# adsr_v3.net
KiCad netlist of a schematic drawn in EAGLE
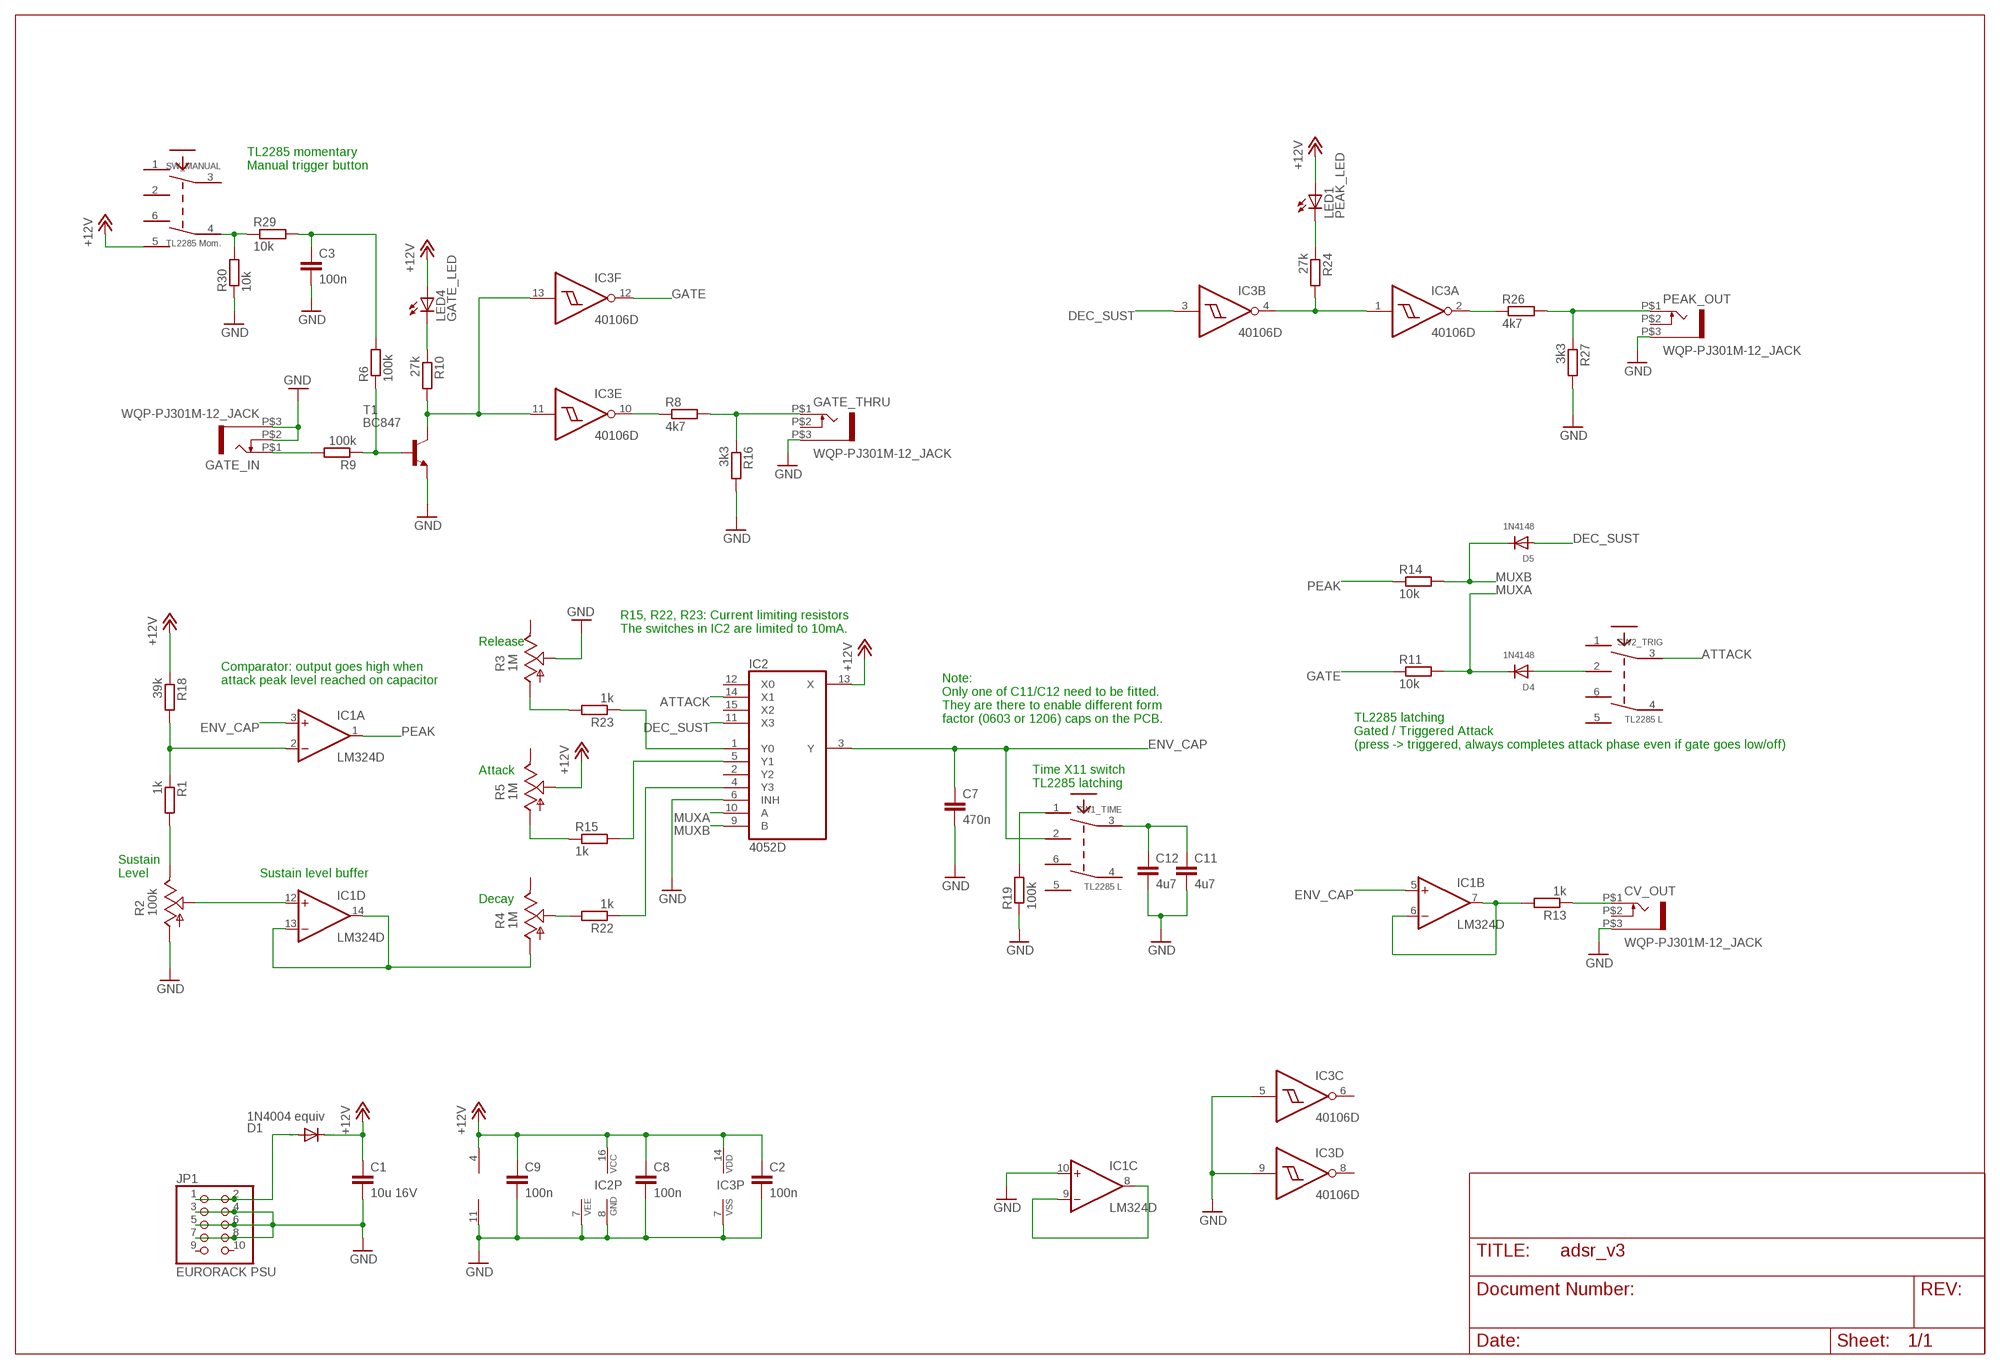
[diagram p0: schematic, sheet 1]

(export (version "E")
  (design (tool "Eeschema 10.0.6"))
  (components
    (comp (ref "C1")
      (value "10u 16V")
      (footprint "eagle-import:C1206K")
      (libsource (lib "eagle-import") (part "C-EUC1206K"))
    )
    (comp (ref "C2")
      (value "100n")
      (footprint "eagle-import:C0603K")
      (libsource (lib "eagle-import") (part "C-EUC0603K"))
    )
    (comp (ref "C3")
      (value "100n")
      (footprint "eagle-import:C0603K")
      (libsource (lib "eagle-import") (part "C-EUC0603K"))
    )
    (comp (ref "C7")
      (value "470n")
      (footprint "eagle-import:C0603K")
      (libsource (lib "eagle-import") (part "C-EUC0603K"))
    )
    (comp (ref "C8")
      (value "100n")
      (footprint "eagle-import:C0603K")
      (libsource (lib "eagle-import") (part "C-EUC0603K"))
    )
    (comp (ref "C9")
      (value "100n")
      (footprint "eagle-import:C0603K")
      (libsource (lib "eagle-import") (part "C-EUC0603K"))
    )
    (comp (ref "C11")
      (value "4u7")
      (footprint "eagle-import:C1206K")
      (libsource (lib "eagle-import") (part "C-EUC1206K"))
    )
    (comp (ref "C12")
      (value "4u7")
      (footprint "eagle-import:C0603K")
      (libsource (lib "eagle-import") (part "C-EUC0603K"))
    )
    (comp (ref "CV_OUT")
      (value "WQP-PJ301M-12_JACK")
      (footprint "eagle-import:WQP-PJ301M-12_JACK")
      (libsource (lib "eagle-import") (part "WQP-PJ301M-12_JACK"))
    )
    (comp (ref "D1")
      (value "1N4004 equiv")
      (footprint "eagle-import:DO214AA")
      (libsource (lib "eagle-import") (part "DIODE-DO214AA"))
    )
    (comp (ref "D4")
      (value "1N4148")
      (footprint "eagle-import:SOD-323F")
      (libsource (lib "eagle-import") (part "DIODESOD-323F"))
    )
    (comp (ref "D5")
      (value "1N4148")
      (footprint "eagle-import:SOD-323F")
      (libsource (lib "eagle-import") (part "DIODESOD-323F"))
    )
    (comp (ref "GATE_IN")
      (value "WQP-PJ301M-12_JACK")
      (footprint "eagle-import:WQP-PJ301M-12_JACK")
      (libsource (lib "eagle-import") (part "WQP-PJ301M-12_JACK"))
    )
    (comp (ref "GATE_THRU")
      (value "WQP-PJ301M-12_JACK")
      (footprint "eagle-import:WQP-PJ301M-12_JACK")
      (libsource (lib "eagle-import") (part "WQP-PJ301M-12_JACK"))
    )
    (comp (ref "IC1")
      (value "LM324D")
      (footprint "eagle-import:SO14")
      (libsource (lib "eagle-import") (part "LM324D"))
    )
    (comp (ref "IC2")
      (value "4052D")
      (footprint "eagle-import:SO16")
      (libsource (lib "eagle-import") (part "4052D"))
    )
    (comp (ref "IC3")
      (value "40106D")
      (footprint "eagle-import:SO14")
      (libsource (lib "eagle-import") (part "40106D"))
    )
    (comp (ref "JP1")
      (value "EURORACK PSU")
      (footprint "eagle-import:2X05")
      (libsource (lib "eagle-import") (part "PINHD-2X5"))
    )
    (comp (ref "LED1")
      (value "PEAK_LED")
      (footprint "eagle-import:LED5MM")
      (libsource (lib "eagle-import") (part "LED5MM"))
    )
    (comp (ref "LED4")
      (value "GATE_LED")
      (footprint "eagle-import:LED5MM")
      (libsource (lib "eagle-import") (part "LED5MM"))
    )
    (comp (ref "PEAK_OUT")
      (value "WQP-PJ301M-12_JACK")
      (footprint "eagle-import:WQP-PJ301M-12_JACK")
      (libsource (lib "eagle-import") (part "WQP-PJ301M-12_JACK"))
    )
    (comp (ref "R1")
      (value "1k")
      (footprint "eagle-import:R0603")
      (libsource (lib "eagle-import") (part "R-EU_R0603"))
    )
    (comp (ref "R2")
      (value "100k")
      (footprint "eagle-import:ALPS_POT_VERTICAL")
      (libsource (lib "eagle-import") (part "POT_USVERTICAL"))
    )
    (comp (ref "R3")
      (value "1M")
      (footprint "eagle-import:ALPS_POT_VERTICAL")
      (libsource (lib "eagle-import") (part "POT_USVERTICAL"))
    )
    (comp (ref "R4")
      (value "1M")
      (footprint "eagle-import:ALPS_POT_VERTICAL")
      (libsource (lib "eagle-import") (part "POT_USVERTICAL"))
    )
    (comp (ref "R5")
      (value "1M")
      (footprint "eagle-import:ALPS_POT_VERTICAL")
      (libsource (lib "eagle-import") (part "POT_USVERTICAL"))
    )
    (comp (ref "R6")
      (value "100k")
      (footprint "eagle-import:R0603")
      (libsource (lib "eagle-import") (part "R-EU_R0603"))
    )
    (comp (ref "R8")
      (value "4k7")
      (footprint "eagle-import:R0603")
      (libsource (lib "eagle-import") (part "R-EU_R0603"))
    )
    (comp (ref "R9")
      (value "100k")
      (footprint "eagle-import:R0603")
      (libsource (lib "eagle-import") (part "R-EU_R0603"))
    )
    (comp (ref "R10")
      (value "27k")
      (footprint "eagle-import:R0603")
      (libsource (lib "eagle-import") (part "R-EU_R0603"))
    )
    (comp (ref "R11")
      (value "10k")
      (footprint "eagle-import:R0603")
      (libsource (lib "eagle-import") (part "R-EU_R0603"))
    )
    (comp (ref "R13")
      (value "1k")
      (footprint "eagle-import:R0603")
      (libsource (lib "eagle-import") (part "R-EU_R0603"))
    )
    (comp (ref "R14")
      (value "10k")
      (footprint "eagle-import:R0603")
      (libsource (lib "eagle-import") (part "R-EU_R0603"))
    )
    (comp (ref "R15")
      (value "1k")
      (footprint "eagle-import:R0603")
      (libsource (lib "eagle-import") (part "R-EU_R0603"))
    )
    (comp (ref "R16")
      (value "3k3")
      (footprint "eagle-import:R0603")
      (libsource (lib "eagle-import") (part "R-EU_R0603"))
    )
    (comp (ref "R18")
      (value "39k")
      (footprint "eagle-import:R0603")
      (libsource (lib "eagle-import") (part "R-EU_R0603"))
    )
    (comp (ref "R19")
      (value "100k")
      (footprint "eagle-import:R0603")
      (libsource (lib "eagle-import") (part "R-EU_R0603"))
    )
    (comp (ref "R22")
      (value "1k")
      (footprint "eagle-import:R0603")
      (libsource (lib "eagle-import") (part "R-EU_R0603"))
    )
    (comp (ref "R23")
      (value "1k")
      (footprint "eagle-import:R0603")
      (libsource (lib "eagle-import") (part "R-EU_R0603"))
    )
    (comp (ref "R24")
      (value "27k")
      (footprint "eagle-import:R0603")
      (libsource (lib "eagle-import") (part "R-EU_R0603"))
    )
    (comp (ref "R26")
      (value "4k7")
      (footprint "eagle-import:R0603")
      (libsource (lib "eagle-import") (part "R-EU_R0603"))
    )
    (comp (ref "R27")
      (value "3k3")
      (footprint "eagle-import:R0603")
      (libsource (lib "eagle-import") (part "R-EU_R0603"))
    )
    (comp (ref "R29")
      (value "10k")
      (footprint "eagle-import:R0603")
      (libsource (lib "eagle-import") (part "R-EU_R0603"))
    )
    (comp (ref "R30")
      (value "10k")
      (footprint "eagle-import:R0603")
      (libsource (lib "eagle-import") (part "R-EU_R0603"))
    )
    (comp (ref "SW1_TIME")
      (value "TL2285 L")
      (footprint "eagle-import:TL2285_PCB")
      (libsource (lib "eagle-import") (part "TL2285"))
    )
    (comp (ref "SW2_TRIG")
      (value "TL2285 L")
      (footprint "eagle-import:TL2285_PCB")
      (libsource (lib "eagle-import") (part "TL2285"))
    )
    (comp (ref "SW_MANUAL")
      (value "TL2285 Mom.")
      (footprint "eagle-import:TL2285_PCB")
      (libsource (lib "eagle-import") (part "TL2285"))
    )
    (comp (ref "T1")
      (value "BC847")
      (footprint "eagle-import:SOT23")
      (libsource (lib "eagle-import") (part "BC847"))
    )
  )
  (nets
    (net (code "1") (name "+12V") (class "Default")
      (node (ref "C1") (pin "1") (pinfunction "1_1") (pintype "passive"))
      (node (ref "C2") (pin "1") (pinfunction "1_1") (pintype "passive"))
      (node (ref "C8") (pin "1") (pinfunction "1_1") (pintype "passive"))
      (node (ref "C9") (pin "1") (pinfunction "1_1") (pintype "passive"))
      (node (ref "D1") (pin "C") (pinfunction "C_C") (pintype "passive"))
      (node (ref "IC1") (pin "4") (pinfunction "V+_4") (pintype "power_in"))
      (node (ref "IC2") (pin "13") (pinfunction "X_13") (pintype "bidirectional"))
      (node (ref "IC2") (pin "16") (pinfunction "VCC_16") (pintype "power_in"))
      (node (ref "IC3") (pin "14") (pinfunction "VDD_14") (pintype "power_in"))
      (node (ref "LED1") (pin "A") (pinfunction "A_A") (pintype "passive"))
      (node (ref "LED4") (pin "A") (pinfunction "A_A") (pintype "passive"))
      (node (ref "R18") (pin "1") (pinfunction "1_1") (pintype "passive"))
      (node (ref "R5") (pin "P$2") (pinfunction "S_P$2") (pintype "passive"))
      (node (ref "SW_MANUAL") (pin "5") (pinfunction "P5_5") (pintype "bidirectional"))
    )
    (net (code "2") (name "/ATTACK") (class "Default")
      (node (ref "IC2") (pin "14") (pinfunction "X1_14") (pintype "bidirectional"))
      (node (ref "SW2_TRIG") (pin "3") (pinfunction "P3_3") (pintype "bidirectional"))
    )
    (net (code "3") (name "/DEC_SUST") (class "Default")
      (node (ref "D5") (pin "A") (pinfunction "A_A") (pintype "passive"))
      (node (ref "IC2") (pin "11") (pinfunction "X3_11") (pintype "bidirectional"))
      (node (ref "IC3") (pin "3") (pinfunction "I_3") (pintype "input"))
    )
    (net (code "4") (name "/ENV_CAP") (class "Default")
      (node (ref "C7") (pin "1") (pinfunction "1_1") (pintype "passive"))
      (node (ref "IC1") (pin "3") (pinfunction "+IN_3") (pintype "input"))
      (node (ref "IC1") (pin "5") (pinfunction "+IN_5") (pintype "input"))
      (node (ref "IC2") (pin "3") (pinfunction "Y_3") (pintype "bidirectional"))
      (node (ref "SW1_TIME") (pin "2") (pinfunction "P2_2") (pintype "bidirectional"))
    )
    (net (code "5") (name "/GATE") (class "Default")
      (node (ref "IC3") (pin "12") (pinfunction "O_12") (pintype "output"))
      (node (ref "R11") (pin "1") (pinfunction "1_1") (pintype "passive"))
    )
    (net (code "6") (name "/MUXA") (class "Default")
      (node (ref "D4") (pin "C") (pinfunction "C_C") (pintype "passive"))
      (node (ref "IC2") (pin "10") (pinfunction "A_10") (pintype "input"))
      (node (ref "R11") (pin "2") (pinfunction "2_2") (pintype "passive"))
    )
    (net (code "7") (name "/MUXB") (class "Default")
      (node (ref "D5") (pin "C") (pinfunction "C_C") (pintype "passive"))
      (node (ref "IC2") (pin "9") (pinfunction "B_9") (pintype "input"))
      (node (ref "R14") (pin "2") (pinfunction "2_2") (pintype "passive"))
    )
    (net (code "8") (name "/PEAK") (class "Default")
      (node (ref "IC1") (pin "1") (pinfunction "OUT_1") (pintype "output"))
      (node (ref "R14") (pin "1") (pinfunction "1_1") (pintype "passive"))
    )
    (net (code "9") (name "GND") (class "Default")
      (node (ref "C1") (pin "2") (pinfunction "2_2") (pintype "passive"))
      (node (ref "C11") (pin "2") (pinfunction "2_2") (pintype "passive"))
      (node (ref "C12") (pin "2") (pinfunction "2_2") (pintype "passive"))
      (node (ref "C2") (pin "2") (pinfunction "2_2") (pintype "passive"))
      (node (ref "C3") (pin "2") (pinfunction "2_2") (pintype "passive"))
      (node (ref "C7") (pin "2") (pinfunction "2_2") (pintype "passive"))
      (node (ref "C8") (pin "2") (pinfunction "2_2") (pintype "passive"))
      (node (ref "C9") (pin "2") (pinfunction "2_2") (pintype "passive"))
      (node (ref "CV_OUT") (pin "P$3") (pinfunction "1_P$3") (pintype "passive"))
      (node (ref "GATE_IN") (pin "P$2") (pinfunction "3_P$2") (pintype "passive"))
      (node (ref "GATE_IN") (pin "P$3") (pinfunction "1_P$3") (pintype "passive"))
      (node (ref "GATE_THRU") (pin "P$3") (pinfunction "1_P$3") (pintype "passive"))
      (node (ref "IC1") (pin "10") (pinfunction "+IN_10") (pintype "input"))
      (node (ref "IC1") (pin "11") (pinfunction "V-_11") (pintype "power_in"))
      (node (ref "IC2") (pin "6") (pinfunction "INH_6") (pintype "input"))
      (node (ref "IC2") (pin "7") (pinfunction "VEE_7") (pintype "power_in"))
      (node (ref "IC2") (pin "8") (pinfunction "GND_8") (pintype "power_in"))
      (node (ref "IC3") (pin "5") (pinfunction "I_5") (pintype "input"))
      (node (ref "IC3") (pin "7") (pinfunction "VSS_7") (pintype "power_in"))
      (node (ref "IC3") (pin "9") (pinfunction "I_9") (pintype "input"))
      (node (ref "JP1") (pin "3") (pinfunction "3_3") (pintype "passive"))
      (node (ref "JP1") (pin "4") (pinfunction "4_4") (pintype "passive"))
      (node (ref "JP1") (pin "5") (pinfunction "5_5") (pintype "passive"))
      (node (ref "JP1") (pin "6") (pinfunction "6_6") (pintype "passive"))
      (node (ref "JP1") (pin "7") (pinfunction "7_7") (pintype "passive"))
      (node (ref "JP1") (pin "8") (pinfunction "8_8") (pintype "passive"))
      (node (ref "PEAK_OUT") (pin "P$3") (pinfunction "1_P$3") (pintype "passive"))
      (node (ref "R16") (pin "2") (pinfunction "2_2") (pintype "passive"))
      (node (ref "R19") (pin "1") (pinfunction "1_1") (pintype "passive"))
      (node (ref "R2") (pin "P$3") (pinfunction "A_P$3") (pintype "passive"))
      (node (ref "R27") (pin "2") (pinfunction "2_2") (pintype "passive"))
      (node (ref "R3") (pin "P$2") (pinfunction "S_P$2") (pintype "passive"))
      (node (ref "R30") (pin "1") (pinfunction "1_1") (pintype "passive"))
      (node (ref "T1") (pin "2") (pinfunction "E_2") (pintype "passive"))
    )
    (net (code "10") (name "Net-(C3-Pad1)") (class "Default")
      (node (ref "C3") (pin "1") (pinfunction "1_1") (pintype "passive"))
      (node (ref "R29") (pin "2") (pinfunction "2_2") (pintype "passive"))
      (node (ref "R6") (pin "2") (pinfunction "2_2") (pintype "passive"))
    )
    (net (code "11") (name "Net-(CV_OUT-2)") (class "Default")
      (node (ref "CV_OUT") (pin "P$1") (pinfunction "2_P$1") (pintype "passive"))
      (node (ref "R13") (pin "1") (pinfunction "1_1") (pintype "passive"))
    )
    (net (code "12") (name "Net-(D1-PadA)") (class "Default")
      (node (ref "D1") (pin "A") (pinfunction "A_A") (pintype "passive"))
      (node (ref "JP1") (pin "1") (pinfunction "1_1") (pintype "passive"))
      (node (ref "JP1") (pin "2") (pinfunction "2_2") (pintype "passive"))
    )
    (net (code "13") (name "Net-(GATE_IN-2)") (class "Default")
      (node (ref "GATE_IN") (pin "P$1") (pinfunction "2_P$1") (pintype "passive"))
      (node (ref "R9") (pin "2") (pinfunction "2_2") (pintype "passive"))
    )
    (net (code "14") (name "Net-(GATE_THRU-2)") (class "Default")
      (node (ref "GATE_THRU") (pin "P$1") (pinfunction "2_P$1") (pintype "passive"))
      (node (ref "R16") (pin "1") (pinfunction "1_1") (pintype "passive"))
      (node (ref "R8") (pin "2") (pinfunction "2_2") (pintype "passive"))
    )
    (net (code "15") (name "Net-(IC1A--IN)") (class "Default")
      (node (ref "IC1") (pin "2") (pinfunction "-IN_2") (pintype "input"))
      (node (ref "R1") (pin "1") (pinfunction "1_1") (pintype "passive"))
      (node (ref "R18") (pin "2") (pinfunction "2_2") (pintype "passive"))
    )
    (net (code "16") (name "Net-(IC1B--IN)") (class "Default")
      (node (ref "IC1") (pin "6") (pinfunction "-IN_6") (pintype "input"))
      (node (ref "IC1") (pin "7") (pinfunction "OUT_7") (pintype "output"))
      (node (ref "R13") (pin "2") (pinfunction "2_2") (pintype "passive"))
    )
    (net (code "17") (name "Net-(IC1C--IN)") (class "Default")
      (node (ref "IC1") (pin "8") (pinfunction "OUT_8") (pintype "output"))
      (node (ref "IC1") (pin "9") (pinfunction "-IN_9") (pintype "input"))
    )
    (net (code "18") (name "Net-(IC1D-+IN)") (class "Default")
      (node (ref "IC1") (pin "12") (pinfunction "+IN_12") (pintype "input"))
      (node (ref "R2") (pin "P$2") (pinfunction "S_P$2") (pintype "passive"))
    )
    (net (code "19") (name "Net-(IC1D--IN)") (class "Default")
      (node (ref "IC1") (pin "13") (pinfunction "-IN_13") (pintype "input"))
      (node (ref "IC1") (pin "14") (pinfunction "OUT_14") (pintype "output"))
      (node (ref "R4") (pin "P$3") (pinfunction "A_P$3") (pintype "passive"))
    )
    (net (code "20") (name "Net-(IC2A-Y0)") (class "Default")
      (node (ref "IC2") (pin "1") (pinfunction "Y0_1") (pintype "bidirectional"))
      (node (ref "R23") (pin "1") (pinfunction "1_1") (pintype "passive"))
    )
    (net (code "21") (name "Net-(IC2A-Y1)") (class "Default")
      (node (ref "IC2") (pin "5") (pinfunction "Y1_5") (pintype "bidirectional"))
      (node (ref "R15") (pin "2") (pinfunction "2_2") (pintype "passive"))
    )
    (net (code "22") (name "Net-(IC2A-Y3)") (class "Default")
      (node (ref "IC2") (pin "4") (pinfunction "Y3_4") (pintype "bidirectional"))
      (node (ref "R22") (pin "1") (pinfunction "1_1") (pintype "passive"))
    )
    (net (code "23") (name "Net-(IC3A-I)") (class "Default")
      (node (ref "IC3") (pin "1") (pinfunction "I_1") (pintype "input"))
      (node (ref "IC3") (pin "4") (pinfunction "O_4") (pintype "output"))
      (node (ref "R24") (pin "2") (pinfunction "2_2") (pintype "passive"))
    )
    (net (code "24") (name "Net-(IC3A-O)") (class "Default")
      (node (ref "IC3") (pin "2") (pinfunction "O_2") (pintype "output"))
      (node (ref "R26") (pin "1") (pinfunction "1_1") (pintype "passive"))
    )
    (net (code "25") (name "Net-(IC3E-I)") (class "Default")
      (node (ref "IC3") (pin "11") (pinfunction "I_11") (pintype "input"))
      (node (ref "IC3") (pin "13") (pinfunction "I_13") (pintype "input"))
      (node (ref "R10") (pin "2") (pinfunction "2_2") (pintype "passive"))
      (node (ref "T1") (pin "3") (pinfunction "C_3") (pintype "passive"))
    )
    (net (code "26") (name "Net-(IC3E-O)") (class "Default")
      (node (ref "IC3") (pin "10") (pinfunction "O_10") (pintype "output"))
      (node (ref "R8") (pin "1") (pinfunction "1_1") (pintype "passive"))
    )
    (net (code "27") (name "Net-(LED1-C)") (class "Default")
      (node (ref "LED1") (pin "K") (pinfunction "C_K") (pintype "passive"))
      (node (ref "R24") (pin "1") (pinfunction "1_1") (pintype "passive"))
    )
    (net (code "28") (name "Net-(LED4-C)") (class "Default")
      (node (ref "LED4") (pin "K") (pinfunction "C_K") (pintype "passive"))
      (node (ref "R10") (pin "1") (pinfunction "1_1") (pintype "passive"))
    )
    (net (code "29") (name "Net-(PEAK_OUT-2)") (class "Default")
      (node (ref "PEAK_OUT") (pin "P$1") (pinfunction "2_P$1") (pintype "passive"))
      (node (ref "R26") (pin "2") (pinfunction "2_2") (pintype "passive"))
      (node (ref "R27") (pin "1") (pinfunction "1_1") (pintype "passive"))
    )
    (net (code "30") (name "Net-(R2-E)") (class "Default")
      (node (ref "R1") (pin "2") (pinfunction "2_2") (pintype "passive"))
      (node (ref "R2") (pin "P$1") (pinfunction "E_P$1") (pintype "passive"))
    )
    (net (code "31") (name "Net-(R3-A)") (class "Default")
      (node (ref "R23") (pin "2") (pinfunction "2_2") (pintype "passive"))
      (node (ref "R3") (pin "P$3") (pinfunction "A_P$3") (pintype "passive"))
    )
    (net (code "32") (name "Net-(R4-S)") (class "Default")
      (node (ref "R22") (pin "2") (pinfunction "2_2") (pintype "passive"))
      (node (ref "R4") (pin "P$2") (pinfunction "S_P$2") (pintype "passive"))
    )
    (net (code "33") (name "Net-(R5-A)") (class "Default")
      (node (ref "R15") (pin "1") (pinfunction "1_1") (pintype "passive"))
      (node (ref "R5") (pin "P$3") (pinfunction "A_P$3") (pintype "passive"))
    )
    (net (code "34") (name "Net-(SW1_TIME-P1)") (class "Default")
      (node (ref "R19") (pin "2") (pinfunction "2_2") (pintype "passive"))
      (node (ref "SW1_TIME") (pin "1") (pinfunction "P1_1") (pintype "bidirectional"))
    )
    (net (code "35") (name "Net-(SW1_TIME-P3)") (class "Default")
      (node (ref "C11") (pin "1") (pinfunction "1_1") (pintype "passive"))
      (node (ref "C12") (pin "1") (pinfunction "1_1") (pintype "passive"))
      (node (ref "SW1_TIME") (pin "3") (pinfunction "P3_3") (pintype "bidirectional"))
    )
    (net (code "36") (name "Net-(SW2_TRIG-P2)") (class "Default")
      (node (ref "D4") (pin "A") (pinfunction "A_A") (pintype "passive"))
      (node (ref "SW2_TRIG") (pin "2") (pinfunction "P2_2") (pintype "bidirectional"))
    )
    (net (code "37") (name "Net-(SW_MANUAL-P4)") (class "Default")
      (node (ref "R29") (pin "1") (pinfunction "1_1") (pintype "passive"))
      (node (ref "R30") (pin "2") (pinfunction "2_2") (pintype "passive"))
      (node (ref "SW_MANUAL") (pin "4") (pinfunction "P4_4") (pintype "bidirectional"))
    )
    (net (code "38") (name "Net-(T1-B)") (class "Default")
      (node (ref "R6") (pin "1") (pinfunction "1_1") (pintype "passive"))
      (node (ref "R9") (pin "1") (pinfunction "1_1") (pintype "passive"))
      (node (ref "T1") (pin "1") (pinfunction "B_1") (pintype "passive"))
    )
    (net (code "39") (name "unconnected-(CV_OUT-3-PadP$2)") (class "Default")
      (node (ref "CV_OUT") (pin "P$2") (pinfunction "3_P$2") (pintype "passive"))
    )
    (net (code "40") (name "unconnected-(GATE_THRU-3-PadP$2)") (class "Default")
      (node (ref "GATE_THRU") (pin "P$2") (pinfunction "3_P$2") (pintype "passive"))
    )
    (net (code "41") (name "unconnected-(IC2A-X0-Pad12)") (class "Default")
      (node (ref "IC2") (pin "12") (pinfunction "X0_12") (pintype "bidirectional"))
    )
    (net (code "42") (name "unconnected-(IC2A-X2-Pad15)") (class "Default")
      (node (ref "IC2") (pin "15") (pinfunction "X2_15") (pintype "bidirectional"))
    )
    (net (code "43") (name "unconnected-(IC2A-Y2-Pad2)") (class "Default")
      (node (ref "IC2") (pin "2") (pinfunction "Y2_2") (pintype "bidirectional"))
    )
    (net (code "44") (name "unconnected-(IC3C-O-Pad6)") (class "Default")
      (node (ref "IC3") (pin "6") (pinfunction "O_6") (pintype "output"))
    )
    (net (code "45") (name "unconnected-(IC3D-O-Pad8)") (class "Default")
      (node (ref "IC3") (pin "8") (pinfunction "O_8") (pintype "output"))
    )
    (net (code "46") (name "unconnected-(JP1-Pad9)") (class "Default")
      (node (ref "JP1") (pin "9") (pinfunction "9_9") (pintype "passive"))
    )
    (net (code "47") (name "unconnected-(JP1-Pad10)") (class "Default")
      (node (ref "JP1") (pin "10") (pinfunction "10_10") (pintype "passive"))
    )
    (net (code "48") (name "unconnected-(PEAK_OUT-3-PadP$2)") (class "Default")
      (node (ref "PEAK_OUT") (pin "P$2") (pinfunction "3_P$2") (pintype "passive"))
    )
    (net (code "49") (name "unconnected-(R3-E-PadP$1)") (class "Default")
      (node (ref "R3") (pin "P$1") (pinfunction "E_P$1") (pintype "passive"))
    )
    (net (code "50") (name "unconnected-(R4-E-PadP$1)") (class "Default")
      (node (ref "R4") (pin "P$1") (pinfunction "E_P$1") (pintype "passive"))
    )
    (net (code "51") (name "unconnected-(R5-E-PadP$1)") (class "Default")
      (node (ref "R5") (pin "P$1") (pinfunction "E_P$1") (pintype "passive"))
    )
    (net (code "52") (name "unconnected-(SW1_TIME-P4-Pad4)") (class "Default")
      (node (ref "SW1_TIME") (pin "4") (pinfunction "P4_4") (pintype "bidirectional"))
    )
    (net (code "53") (name "unconnected-(SW1_TIME-P5-Pad5)") (class "Default")
      (node (ref "SW1_TIME") (pin "5") (pinfunction "P5_5") (pintype "bidirectional"))
    )
    (net (code "54") (name "unconnected-(SW1_TIME-P6-Pad6)") (class "Default")
      (node (ref "SW1_TIME") (pin "6") (pinfunction "P6_6") (pintype "bidirectional"))
    )
    (net (code "55") (name "unconnected-(SW2_TRIG-P1-Pad1)") (class "Default")
      (node (ref "SW2_TRIG") (pin "1") (pinfunction "P1_1") (pintype "bidirectional"))
    )
    (net (code "56") (name "unconnected-(SW2_TRIG-P4-Pad4)") (class "Default")
      (node (ref "SW2_TRIG") (pin "4") (pinfunction "P4_4") (pintype "bidirectional"))
    )
    (net (code "57") (name "unconnected-(SW2_TRIG-P5-Pad5)") (class "Default")
      (node (ref "SW2_TRIG") (pin "5") (pinfunction "P5_5") (pintype "bidirectional"))
    )
    (net (code "58") (name "unconnected-(SW2_TRIG-P6-Pad6)") (class "Default")
      (node (ref "SW2_TRIG") (pin "6") (pinfunction "P6_6") (pintype "bidirectional"))
    )
    (net (code "59") (name "unconnected-(SW_MANUAL-P1-Pad1)") (class "Default")
      (node (ref "SW_MANUAL") (pin "1") (pinfunction "P1_1") (pintype "bidirectional"))
    )
    (net (code "60") (name "unconnected-(SW_MANUAL-P2-Pad2)") (class "Default")
      (node (ref "SW_MANUAL") (pin "2") (pinfunction "P2_2") (pintype "bidirectional"))
    )
    (net (code "61") (name "unconnected-(SW_MANUAL-P3-Pad3)") (class "Default")
      (node (ref "SW_MANUAL") (pin "3") (pinfunction "P3_3") (pintype "bidirectional"))
    )
    (net (code "62") (name "unconnected-(SW_MANUAL-P6-Pad6)") (class "Default")
      (node (ref "SW_MANUAL") (pin "6") (pinfunction "P6_6") (pintype "bidirectional"))
    )
  )
)
